# V0_2.net
KiCad netlist of a schematic drawn in EAGLE
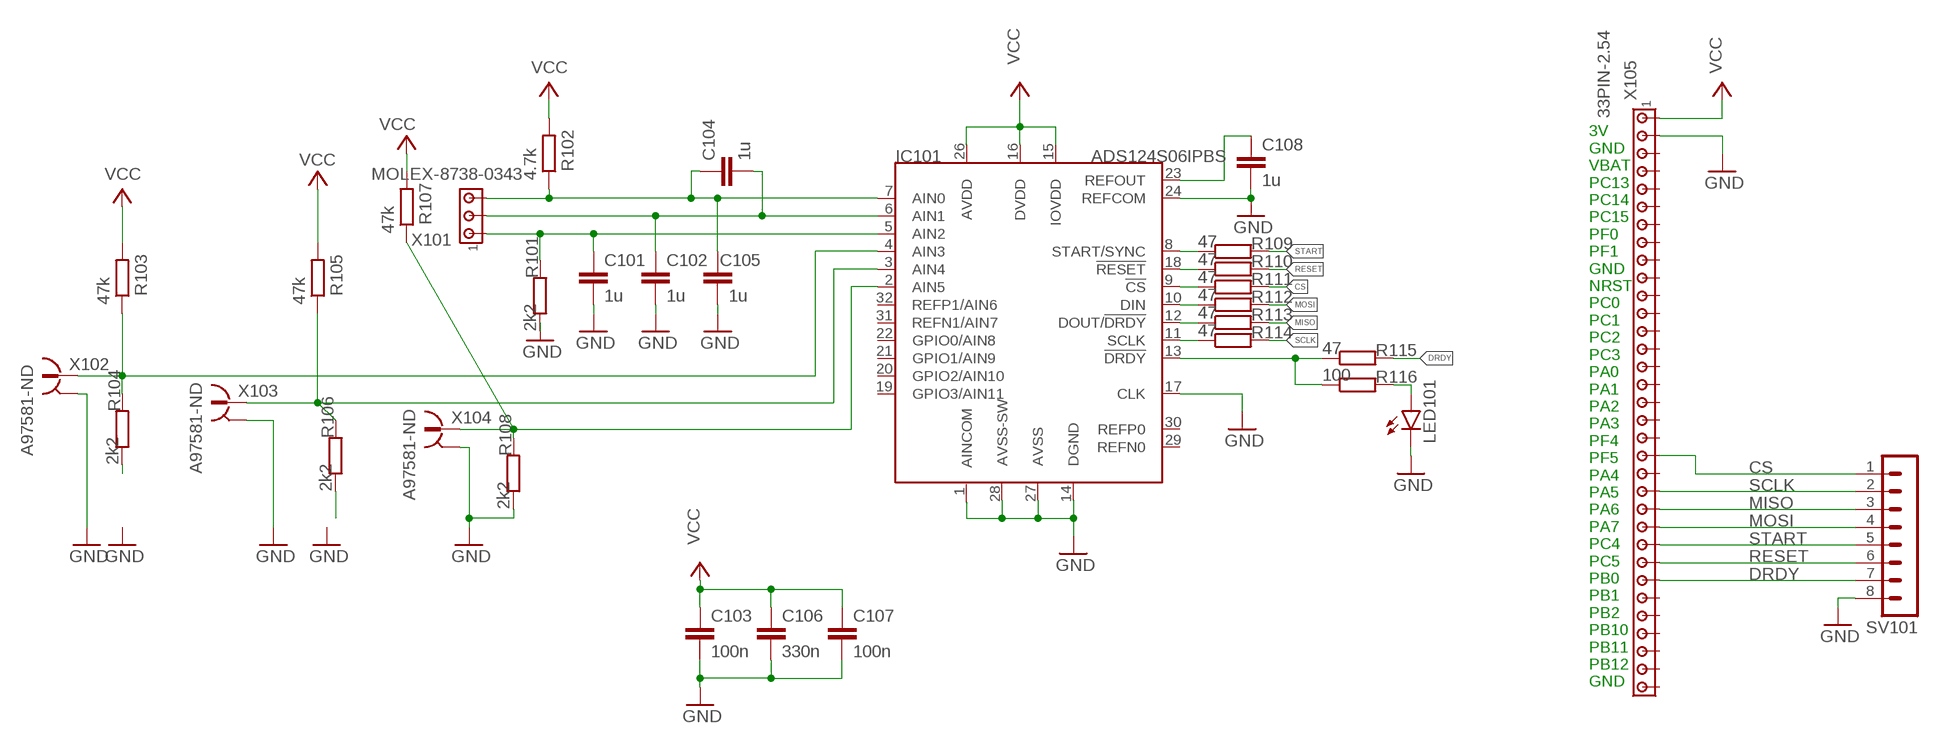
[diagram p0: schematic, sheet 1]

(export (version "E")
  (design (tool "Eeschema 10.0.6"))
  (components
    (comp (ref "C101")
      (value "1u")
      (footprint "eagle-import:C0603")
      (libsource (lib "eagle-import") (part "C-EUC0603"))
    )
    (comp (ref "C102")
      (value "1u")
      (footprint "eagle-import:C0603")
      (libsource (lib "eagle-import") (part "C-EUC0603"))
    )
    (comp (ref "C103")
      (value "100n")
      (footprint "eagle-import:C0603")
      (libsource (lib "eagle-import") (part "C-EUC0603"))
    )
    (comp (ref "C104")
      (value "1u")
      (footprint "eagle-import:C0603")
      (libsource (lib "eagle-import") (part "C-EUC0603"))
    )
    (comp (ref "C105")
      (value "1u")
      (footprint "eagle-import:C0603")
      (libsource (lib "eagle-import") (part "C-EUC0603"))
    )
    (comp (ref "C106")
      (value "330n")
      (footprint "eagle-import:C0603")
      (libsource (lib "eagle-import") (part "C-EUC0603"))
    )
    (comp (ref "C107")
      (value "100n")
      (footprint "eagle-import:C0603")
      (libsource (lib "eagle-import") (part "C-EUC0603"))
    )
    (comp (ref "C108")
      (value "1u")
      (footprint "eagle-import:C0603")
      (libsource (lib "eagle-import") (part "C-EUC0603"))
    )
    (comp (ref "IC101")
      (value "ADS124S06IPBS")
      (footprint "eagle-import:TQFP32-05")
      (libsource (lib "eagle-import") (part "ADS124S0XIPBS"))
    )
    (comp (ref "LED101")
      (value "LEDSML0603")
      (footprint "eagle-import:SML0603")
      (libsource (lib "eagle-import") (part "LEDSML0603"))
    )
    (comp (ref "R101")
      (value "2k2")
      (footprint "eagle-import:R0805W")
      (libsource (lib "eagle-import") (part "R-EU_R0805W"))
    )
    (comp (ref "R102")
      (value "4.7k")
      (footprint "eagle-import:R0603")
      (libsource (lib "eagle-import") (part "R-EU_R0603"))
    )
    (comp (ref "R103")
      (value "47k")
      (footprint "eagle-import:R0603")
      (libsource (lib "eagle-import") (part "R-EU_R0603"))
    )
    (comp (ref "R104")
      (value "2k2")
      (footprint "eagle-import:R0805W")
      (libsource (lib "eagle-import") (part "R-EU_R0805W"))
    )
    (comp (ref "R105")
      (value "47k")
      (footprint "eagle-import:R0603")
      (libsource (lib "eagle-import") (part "R-EU_R0603"))
    )
    (comp (ref "R106")
      (value "2k2")
      (footprint "eagle-import:R0805W")
      (libsource (lib "eagle-import") (part "R-EU_R0805W"))
    )
    (comp (ref "R107")
      (value "47k")
      (footprint "eagle-import:R0603")
      (libsource (lib "eagle-import") (part "R-EU_R0603"))
    )
    (comp (ref "R108")
      (value "2k2")
      (footprint "eagle-import:R0805W")
      (libsource (lib "eagle-import") (part "R-EU_R0805W"))
    )
    (comp (ref "R109")
      (value "47")
      (footprint "eagle-import:R0603")
      (libsource (lib "eagle-import") (part "R-EU_R0603"))
    )
    (comp (ref "R110")
      (value "47")
      (footprint "eagle-import:R0603")
      (libsource (lib "eagle-import") (part "R-EU_R0603"))
    )
    (comp (ref "R111")
      (value "47")
      (footprint "eagle-import:R0603")
      (libsource (lib "eagle-import") (part "R-EU_R0603"))
    )
    (comp (ref "R112")
      (value "47")
      (footprint "eagle-import:R0603")
      (libsource (lib "eagle-import") (part "R-EU_R0603"))
    )
    (comp (ref "R113")
      (value "47")
      (footprint "eagle-import:R0603")
      (libsource (lib "eagle-import") (part "R-EU_R0603"))
    )
    (comp (ref "R114")
      (value "47")
      (footprint "eagle-import:R0603")
      (libsource (lib "eagle-import") (part "R-EU_R0603"))
    )
    (comp (ref "R115")
      (value "47")
      (footprint "eagle-import:R0603")
      (libsource (lib "eagle-import") (part "R-EU_R0603"))
    )
    (comp (ref "R116")
      (value "100")
      (footprint "eagle-import:R0603")
      (libsource (lib "eagle-import") (part "R-EU_R0603"))
    )
    (comp (ref "SV101")
      (value "MA08-1")
      (footprint "eagle-import:MA08-1")
      (libsource (lib "eagle-import") (part "MA08-1"))
    )
    (comp (ref "X101")
      (value "MOLEX-8738-0343")
      (footprint "eagle-import:MOLEX-87438-0343")
      (libsource (lib "eagle-import") (part "MOLEX-8738-0343"))
    )
    (comp (ref "X102")
      (value "A97581-ND")
      (footprint "eagle-import:1634503")
      (libsource (lib "eagle-import") (part "A97581-ND"))
    )
    (comp (ref "X103")
      (value "A97581-ND")
      (footprint "eagle-import:1634503")
      (libsource (lib "eagle-import") (part "A97581-ND"))
    )
    (comp (ref "X104")
      (value "A97581-ND")
      (footprint "eagle-import:1634503")
      (libsource (lib "eagle-import") (part "A97581-ND"))
    )
    (comp (ref "X105")
      (value "33PIN-2.54")
      (footprint "eagle-import:1X33")
      (libsource (lib "eagle-import") (part "33PIN-2.54"))
    )
  )
  (nets
    (net (code "1") (name "CS") (class "Default")
      (node (ref "R111") (pin "2") (pinfunction "2_2") (pintype "passive"))
      (node (ref "SV101") (pin "1") (pinfunction "1_1") (pintype "passive"))
      (node (ref "X105") (pin "20") (pinfunction "20_20") (pintype "passive"))
    )
    (net (code "2") (name "DRDY") (class "Default")
      (node (ref "R115") (pin "2") (pinfunction "2_2") (pintype "passive"))
      (node (ref "SV101") (pin "7") (pinfunction "7_7") (pintype "passive"))
      (node (ref "X105") (pin "27") (pinfunction "27_27") (pintype "passive"))
    )
    (net (code "3") (name "GND") (class "Default")
      (node (ref "C101") (pin "2") (pinfunction "2_2") (pintype "passive"))
      (node (ref "C102") (pin "2") (pinfunction "2_2") (pintype "passive"))
      (node (ref "C103") (pin "2") (pinfunction "2_2") (pintype "passive"))
      (node (ref "C105") (pin "2") (pinfunction "2_2") (pintype "passive"))
      (node (ref "C106") (pin "2") (pinfunction "2_2") (pintype "passive"))
      (node (ref "C107") (pin "2") (pinfunction "2_2") (pintype "passive"))
      (node (ref "C108") (pin "2") (pinfunction "2_2") (pintype "passive"))
      (node (ref "IC101") (pin "1") (pinfunction "AINCOM_1") (pintype "bidirectional"))
      (node (ref "IC101") (pin "14") (pinfunction "DGND_14") (pintype "bidirectional"))
      (node (ref "IC101") (pin "17") (pinfunction "CLK_17") (pintype "bidirectional"))
      (node (ref "IC101") (pin "24") (pinfunction "REFCOM_24") (pintype "bidirectional"))
      (node (ref "IC101") (pin "27") (pinfunction "AVSS_27") (pintype "bidirectional"))
      (node (ref "IC101") (pin "28") (pinfunction "AVSS-SW_28") (pintype "bidirectional"))
      (node (ref "LED101") (pin "C") (pinfunction "C_C") (pintype "passive"))
      (node (ref "R101") (pin "1") (pinfunction "1_1") (pintype "passive"))
      (node (ref "R108") (pin "1") (pinfunction "1_1") (pintype "passive"))
      (node (ref "SV101") (pin "8") (pinfunction "8_8") (pintype "passive"))
      (node (ref "X102") (pin "2") (pinfunction "2_2") (pintype "passive"))
      (node (ref "X102") (pin "3") (pinfunction "2_3") (pintype "passive"))
      (node (ref "X102") (pin "4") (pinfunction "2_4") (pintype "passive"))
      (node (ref "X102") (pin "5") (pinfunction "2_5") (pintype "passive"))
      (node (ref "X103") (pin "2") (pinfunction "2_2") (pintype "passive"))
      (node (ref "X103") (pin "3") (pinfunction "2_3") (pintype "passive"))
      (node (ref "X103") (pin "4") (pinfunction "2_4") (pintype "passive"))
      (node (ref "X103") (pin "5") (pinfunction "2_5") (pintype "passive"))
      (node (ref "X104") (pin "2") (pinfunction "2_2") (pintype "passive"))
      (node (ref "X104") (pin "3") (pinfunction "2_3") (pintype "passive"))
      (node (ref "X104") (pin "4") (pinfunction "2_4") (pintype "passive"))
      (node (ref "X104") (pin "5") (pinfunction "2_5") (pintype "passive"))
      (node (ref "X105") (pin "2") (pinfunction "2_2") (pintype "passive"))
    )
    (net (code "4") (name "MISO") (class "Default")
      (node (ref "R113") (pin "2") (pinfunction "2_2") (pintype "passive"))
      (node (ref "SV101") (pin "3") (pinfunction "3_3") (pintype "passive"))
      (node (ref "X105") (pin "23") (pinfunction "23_23") (pintype "passive"))
    )
    (net (code "5") (name "MOSI") (class "Default")
      (node (ref "R112") (pin "2") (pinfunction "2_2") (pintype "passive"))
      (node (ref "SV101") (pin "4") (pinfunction "4_4") (pintype "passive"))
      (node (ref "X105") (pin "24") (pinfunction "24_24") (pintype "passive"))
    )
    (net (code "6") (name "Net-(IC101-AIN0)") (class "Default")
      (node (ref "C104") (pin "1") (pinfunction "1_1") (pintype "passive"))
      (node (ref "C105") (pin "1") (pinfunction "1_1") (pintype "passive"))
      (node (ref "IC101") (pin "7") (pinfunction "AIN0_7") (pintype "bidirectional"))
      (node (ref "R102") (pin "1") (pinfunction "1_1") (pintype "passive"))
      (node (ref "X101") (pin "3") (pinfunction "3_3") (pintype "passive"))
      (node (ref "X101") (pin "3_1") (pinfunction "3_3_1") (pintype "passive"))
    )
    (net (code "7") (name "Net-(IC101-AIN1)") (class "Default")
      (node (ref "C102") (pin "1") (pinfunction "1_1") (pintype "passive"))
      (node (ref "C104") (pin "2") (pinfunction "2_2") (pintype "passive"))
      (node (ref "IC101") (pin "6") (pinfunction "AIN1_6") (pintype "bidirectional"))
      (node (ref "X101") (pin "2") (pinfunction "2_2") (pintype "passive"))
      (node (ref "X101") (pin "2_1") (pinfunction "2_2_1") (pintype "passive"))
    )
    (net (code "8") (name "Net-(IC101-AIN2)") (class "Default")
      (node (ref "C101") (pin "1") (pinfunction "1_1") (pintype "passive"))
      (node (ref "IC101") (pin "5") (pinfunction "AIN2_5") (pintype "bidirectional"))
      (node (ref "R101") (pin "2") (pinfunction "2_2") (pintype "passive"))
      (node (ref "X101") (pin "1") (pinfunction "1_1") (pintype "passive"))
      (node (ref "X101") (pin "1_1") (pinfunction "1_1_1") (pintype "passive"))
    )
    (net (code "9") (name "Net-(IC101-AIN3)") (class "Default")
      (node (ref "IC101") (pin "4") (pinfunction "AIN3_4") (pintype "bidirectional"))
      (node (ref "R103") (pin "1") (pinfunction "1_1") (pintype "passive"))
      (node (ref "R104") (pin "2") (pinfunction "2_2") (pintype "passive"))
      (node (ref "X102") (pin "1") (pinfunction "1_1") (pintype "passive"))
    )
    (net (code "10") (name "Net-(IC101-AIN4)") (class "Default")
      (node (ref "IC101") (pin "3") (pinfunction "AIN4_3") (pintype "bidirectional"))
      (node (ref "R105") (pin "1") (pinfunction "1_1") (pintype "passive"))
      (node (ref "R106") (pin "2") (pinfunction "2_2") (pintype "passive"))
      (node (ref "X103") (pin "1") (pinfunction "1_1") (pintype "passive"))
    )
    (net (code "11") (name "Net-(IC101-AIN5)") (class "Default")
      (node (ref "IC101") (pin "2") (pinfunction "AIN5_2") (pintype "bidirectional"))
      (node (ref "R107") (pin "1") (pinfunction "1_1") (pintype "passive"))
      (node (ref "R108") (pin "2") (pinfunction "2_2") (pintype "passive"))
      (node (ref "X104") (pin "1") (pinfunction "1_1") (pintype "passive"))
    )
    (net (code "12") (name "Net-(IC101-DIN)") (class "Default")
      (node (ref "IC101") (pin "10") (pinfunction "DIN_10") (pintype "bidirectional"))
      (node (ref "R112") (pin "1") (pinfunction "1_1") (pintype "passive"))
    )
    (net (code "13") (name "Net-(IC101-DOUT{slash}~{DRDY})") (class "Default")
      (node (ref "IC101") (pin "12") (pinfunction "DOUT/~{DRDY}_12") (pintype "bidirectional"))
      (node (ref "R113") (pin "1") (pinfunction "1_1") (pintype "passive"))
    )
    (net (code "14") (name "Net-(IC101-REFOUT)") (class "Default")
      (node (ref "C108") (pin "1") (pinfunction "1_1") (pintype "passive"))
      (node (ref "IC101") (pin "23") (pinfunction "REFOUT_23") (pintype "bidirectional"))
    )
    (net (code "15") (name "Net-(IC101-SCLK)") (class "Default")
      (node (ref "IC101") (pin "11") (pinfunction "SCLK_11") (pintype "bidirectional"))
      (node (ref "R114") (pin "1") (pinfunction "1_1") (pintype "passive"))
    )
    (net (code "16") (name "Net-(IC101-START{slash}SYNC)") (class "Default")
      (node (ref "IC101") (pin "8") (pinfunction "START/SYNC_8") (pintype "bidirectional"))
      (node (ref "R109") (pin "1") (pinfunction "1_1") (pintype "passive"))
    )
    (net (code "17") (name "Net-(IC101-~{CS})") (class "Default")
      (node (ref "IC101") (pin "9") (pinfunction "~{CS}_9") (pintype "bidirectional"))
      (node (ref "R111") (pin "1") (pinfunction "1_1") (pintype "passive"))
    )
    (net (code "18") (name "Net-(IC101-~{DRDY})") (class "Default")
      (node (ref "IC101") (pin "13") (pinfunction "~{DRDY}_13") (pintype "bidirectional"))
      (node (ref "R115") (pin "1") (pinfunction "1_1") (pintype "passive"))
      (node (ref "R116") (pin "1") (pinfunction "1_1") (pintype "passive"))
    )
    (net (code "19") (name "Net-(IC101-~{RESET})") (class "Default")
      (node (ref "IC101") (pin "18") (pinfunction "~{RESET}_18") (pintype "bidirectional"))
      (node (ref "R110") (pin "1") (pinfunction "1_1") (pintype "passive"))
    )
    (net (code "20") (name "Net-(LED101-PadA)") (class "Default")
      (node (ref "LED101") (pin "A") (pinfunction "A_A") (pintype "passive"))
      (node (ref "R116") (pin "2") (pinfunction "2_2") (pintype "passive"))
    )
    (net (code "21") (name "RESET") (class "Default")
      (node (ref "R110") (pin "2") (pinfunction "2_2") (pintype "passive"))
      (node (ref "SV101") (pin "6") (pinfunction "6_6") (pintype "passive"))
      (node (ref "X105") (pin "26") (pinfunction "26_26") (pintype "passive"))
    )
    (net (code "22") (name "SCLK") (class "Default")
      (node (ref "R114") (pin "2") (pinfunction "2_2") (pintype "passive"))
      (node (ref "SV101") (pin "2") (pinfunction "2_2") (pintype "passive"))
      (node (ref "X105") (pin "22") (pinfunction "22_22") (pintype "passive"))
    )
    (net (code "23") (name "START") (class "Default")
      (node (ref "R109") (pin "2") (pinfunction "2_2") (pintype "passive"))
      (node (ref "SV101") (pin "5") (pinfunction "5_5") (pintype "passive"))
      (node (ref "X105") (pin "25") (pinfunction "25_25") (pintype "passive"))
    )
    (net (code "24") (name "VCC") (class "Default")
      (node (ref "C103") (pin "1") (pinfunction "1_1") (pintype "passive"))
      (node (ref "C106") (pin "1") (pinfunction "1_1") (pintype "passive"))
      (node (ref "C107") (pin "1") (pinfunction "1_1") (pintype "passive"))
      (node (ref "IC101") (pin "15") (pinfunction "IOVDD_15") (pintype "bidirectional"))
      (node (ref "IC101") (pin "16") (pinfunction "DVDD_16") (pintype "bidirectional"))
      (node (ref "IC101") (pin "26") (pinfunction "AVDD_26") (pintype "bidirectional"))
      (node (ref "R102") (pin "2") (pinfunction "2_2") (pintype "passive"))
      (node (ref "R103") (pin "2") (pinfunction "2_2") (pintype "passive"))
      (node (ref "R105") (pin "2") (pinfunction "2_2") (pintype "passive"))
      (node (ref "R107") (pin "2") (pinfunction "2_2") (pintype "passive"))
      (node (ref "X105") (pin "1") (pinfunction "1_1") (pintype "passive"))
    )
    (net (code "25") (name "unconnected-(IC101-GPIO0{slash}AIN8-Pad22)") (class "Default")
      (node (ref "IC101") (pin "22") (pinfunction "GPIO0/AIN8_22") (pintype "bidirectional"))
    )
    (net (code "26") (name "unconnected-(IC101-GPIO1{slash}AIN9-Pad21)") (class "Default")
      (node (ref "IC101") (pin "21") (pinfunction "GPIO1/AIN9_21") (pintype "bidirectional"))
    )
    (net (code "27") (name "unconnected-(IC101-GPIO2{slash}AIN10-Pad20)") (class "Default")
      (node (ref "IC101") (pin "20") (pinfunction "GPIO2/AIN10_20") (pintype "bidirectional"))
    )
    (net (code "28") (name "unconnected-(IC101-GPIO3{slash}AIN11-Pad19)") (class "Default")
      (node (ref "IC101") (pin "19") (pinfunction "GPIO3/AIN11_19") (pintype "bidirectional"))
    )
    (net (code "29") (name "unconnected-(IC101-REFN0-Pad29)") (class "Default")
      (node (ref "IC101") (pin "29") (pinfunction "REFN0_29") (pintype "bidirectional"))
    )
    (net (code "30") (name "unconnected-(IC101-REFN1{slash}AIN7-Pad31)") (class "Default")
      (node (ref "IC101") (pin "31") (pinfunction "REFN1/AIN7_31") (pintype "bidirectional"))
    )
    (net (code "31") (name "unconnected-(IC101-REFP0-Pad30)") (class "Default")
      (node (ref "IC101") (pin "30") (pinfunction "REFP0_30") (pintype "bidirectional"))
    )
    (net (code "32") (name "unconnected-(IC101-REFP1{slash}AIN6-Pad32)") (class "Default")
      (node (ref "IC101") (pin "32") (pinfunction "REFP1/AIN6_32") (pintype "bidirectional"))
    )
    (net (code "33") (name "unconnected-(R104-Pad1)") (class "Default")
      (node (ref "R104") (pin "1") (pinfunction "1_1") (pintype "passive"))
    )
    (net (code "34") (name "unconnected-(R106-Pad1)") (class "Default")
      (node (ref "R106") (pin "1") (pinfunction "1_1") (pintype "passive"))
    )
    (net (code "35") (name "unconnected-(X105-Pad3)") (class "Default")
      (node (ref "X105") (pin "3") (pinfunction "3_3") (pintype "passive"))
    )
    (net (code "36") (name "unconnected-(X105-Pad4)") (class "Default")
      (node (ref "X105") (pin "4") (pinfunction "4_4") (pintype "passive"))
    )
    (net (code "37") (name "unconnected-(X105-Pad5)") (class "Default")
      (node (ref "X105") (pin "5") (pinfunction "5_5") (pintype "passive"))
    )
    (net (code "38") (name "unconnected-(X105-Pad6)") (class "Default")
      (node (ref "X105") (pin "6") (pinfunction "6_6") (pintype "passive"))
    )
    (net (code "39") (name "unconnected-(X105-Pad7)") (class "Default")
      (node (ref "X105") (pin "7") (pinfunction "7_7") (pintype "passive"))
    )
    (net (code "40") (name "unconnected-(X105-Pad8)") (class "Default")
      (node (ref "X105") (pin "8") (pinfunction "8_8") (pintype "passive"))
    )
    (net (code "41") (name "unconnected-(X105-Pad9)") (class "Default")
      (node (ref "X105") (pin "9") (pinfunction "9_9") (pintype "passive"))
    )
    (net (code "42") (name "unconnected-(X105-Pad10)") (class "Default")
      (node (ref "X105") (pin "10") (pinfunction "10_10") (pintype "passive"))
    )
    (net (code "43") (name "unconnected-(X105-Pad11)") (class "Default")
      (node (ref "X105") (pin "11") (pinfunction "11_11") (pintype "passive"))
    )
    (net (code "44") (name "unconnected-(X105-Pad12)") (class "Default")
      (node (ref "X105") (pin "12") (pinfunction "12_12") (pintype "passive"))
    )
    (net (code "45") (name "unconnected-(X105-Pad13)") (class "Default")
      (node (ref "X105") (pin "13") (pinfunction "13_13") (pintype "passive"))
    )
    (net (code "46") (name "unconnected-(X105-Pad14)") (class "Default")
      (node (ref "X105") (pin "14") (pinfunction "14_14") (pintype "passive"))
    )
    (net (code "47") (name "unconnected-(X105-Pad15)") (class "Default")
      (node (ref "X105") (pin "15") (pinfunction "15_15") (pintype "passive"))
    )
    (net (code "48") (name "unconnected-(X105-Pad16)") (class "Default")
      (node (ref "X105") (pin "16") (pinfunction "16_16") (pintype "passive"))
    )
    (net (code "49") (name "unconnected-(X105-Pad17)") (class "Default")
      (node (ref "X105") (pin "17") (pinfunction "17_17") (pintype "passive"))
    )
    (net (code "50") (name "unconnected-(X105-Pad18)") (class "Default")
      (node (ref "X105") (pin "18") (pinfunction "18_18") (pintype "passive"))
    )
    (net (code "51") (name "unconnected-(X105-Pad19)") (class "Default")
      (node (ref "X105") (pin "19") (pinfunction "19_19") (pintype "passive"))
    )
    (net (code "52") (name "unconnected-(X105-Pad21)") (class "Default")
      (node (ref "X105") (pin "21") (pinfunction "21_21") (pintype "passive"))
    )
    (net (code "53") (name "unconnected-(X105-Pad28)") (class "Default")
      (node (ref "X105") (pin "28") (pinfunction "28_28") (pintype "passive"))
    )
    (net (code "54") (name "unconnected-(X105-Pad29)") (class "Default")
      (node (ref "X105") (pin "29") (pinfunction "29_29") (pintype "passive"))
    )
    (net (code "55") (name "unconnected-(X105-Pad30)") (class "Default")
      (node (ref "X105") (pin "30") (pinfunction "30_30") (pintype "passive"))
    )
    (net (code "56") (name "unconnected-(X105-Pad31)") (class "Default")
      (node (ref "X105") (pin "31") (pinfunction "31_31") (pintype "passive"))
    )
    (net (code "57") (name "unconnected-(X105-Pad32)") (class "Default")
      (node (ref "X105") (pin "32") (pinfunction "32_32") (pintype "passive"))
    )
    (net (code "58") (name "unconnected-(X105-Pad33)") (class "Default")
      (node (ref "X105") (pin "33") (pinfunction "33_33") (pintype "passive"))
    )
  )
)
